# SCH_Broke-Knomi_2026-06-14.net
KiCad netlist of a schematic drawn in EasyEDA
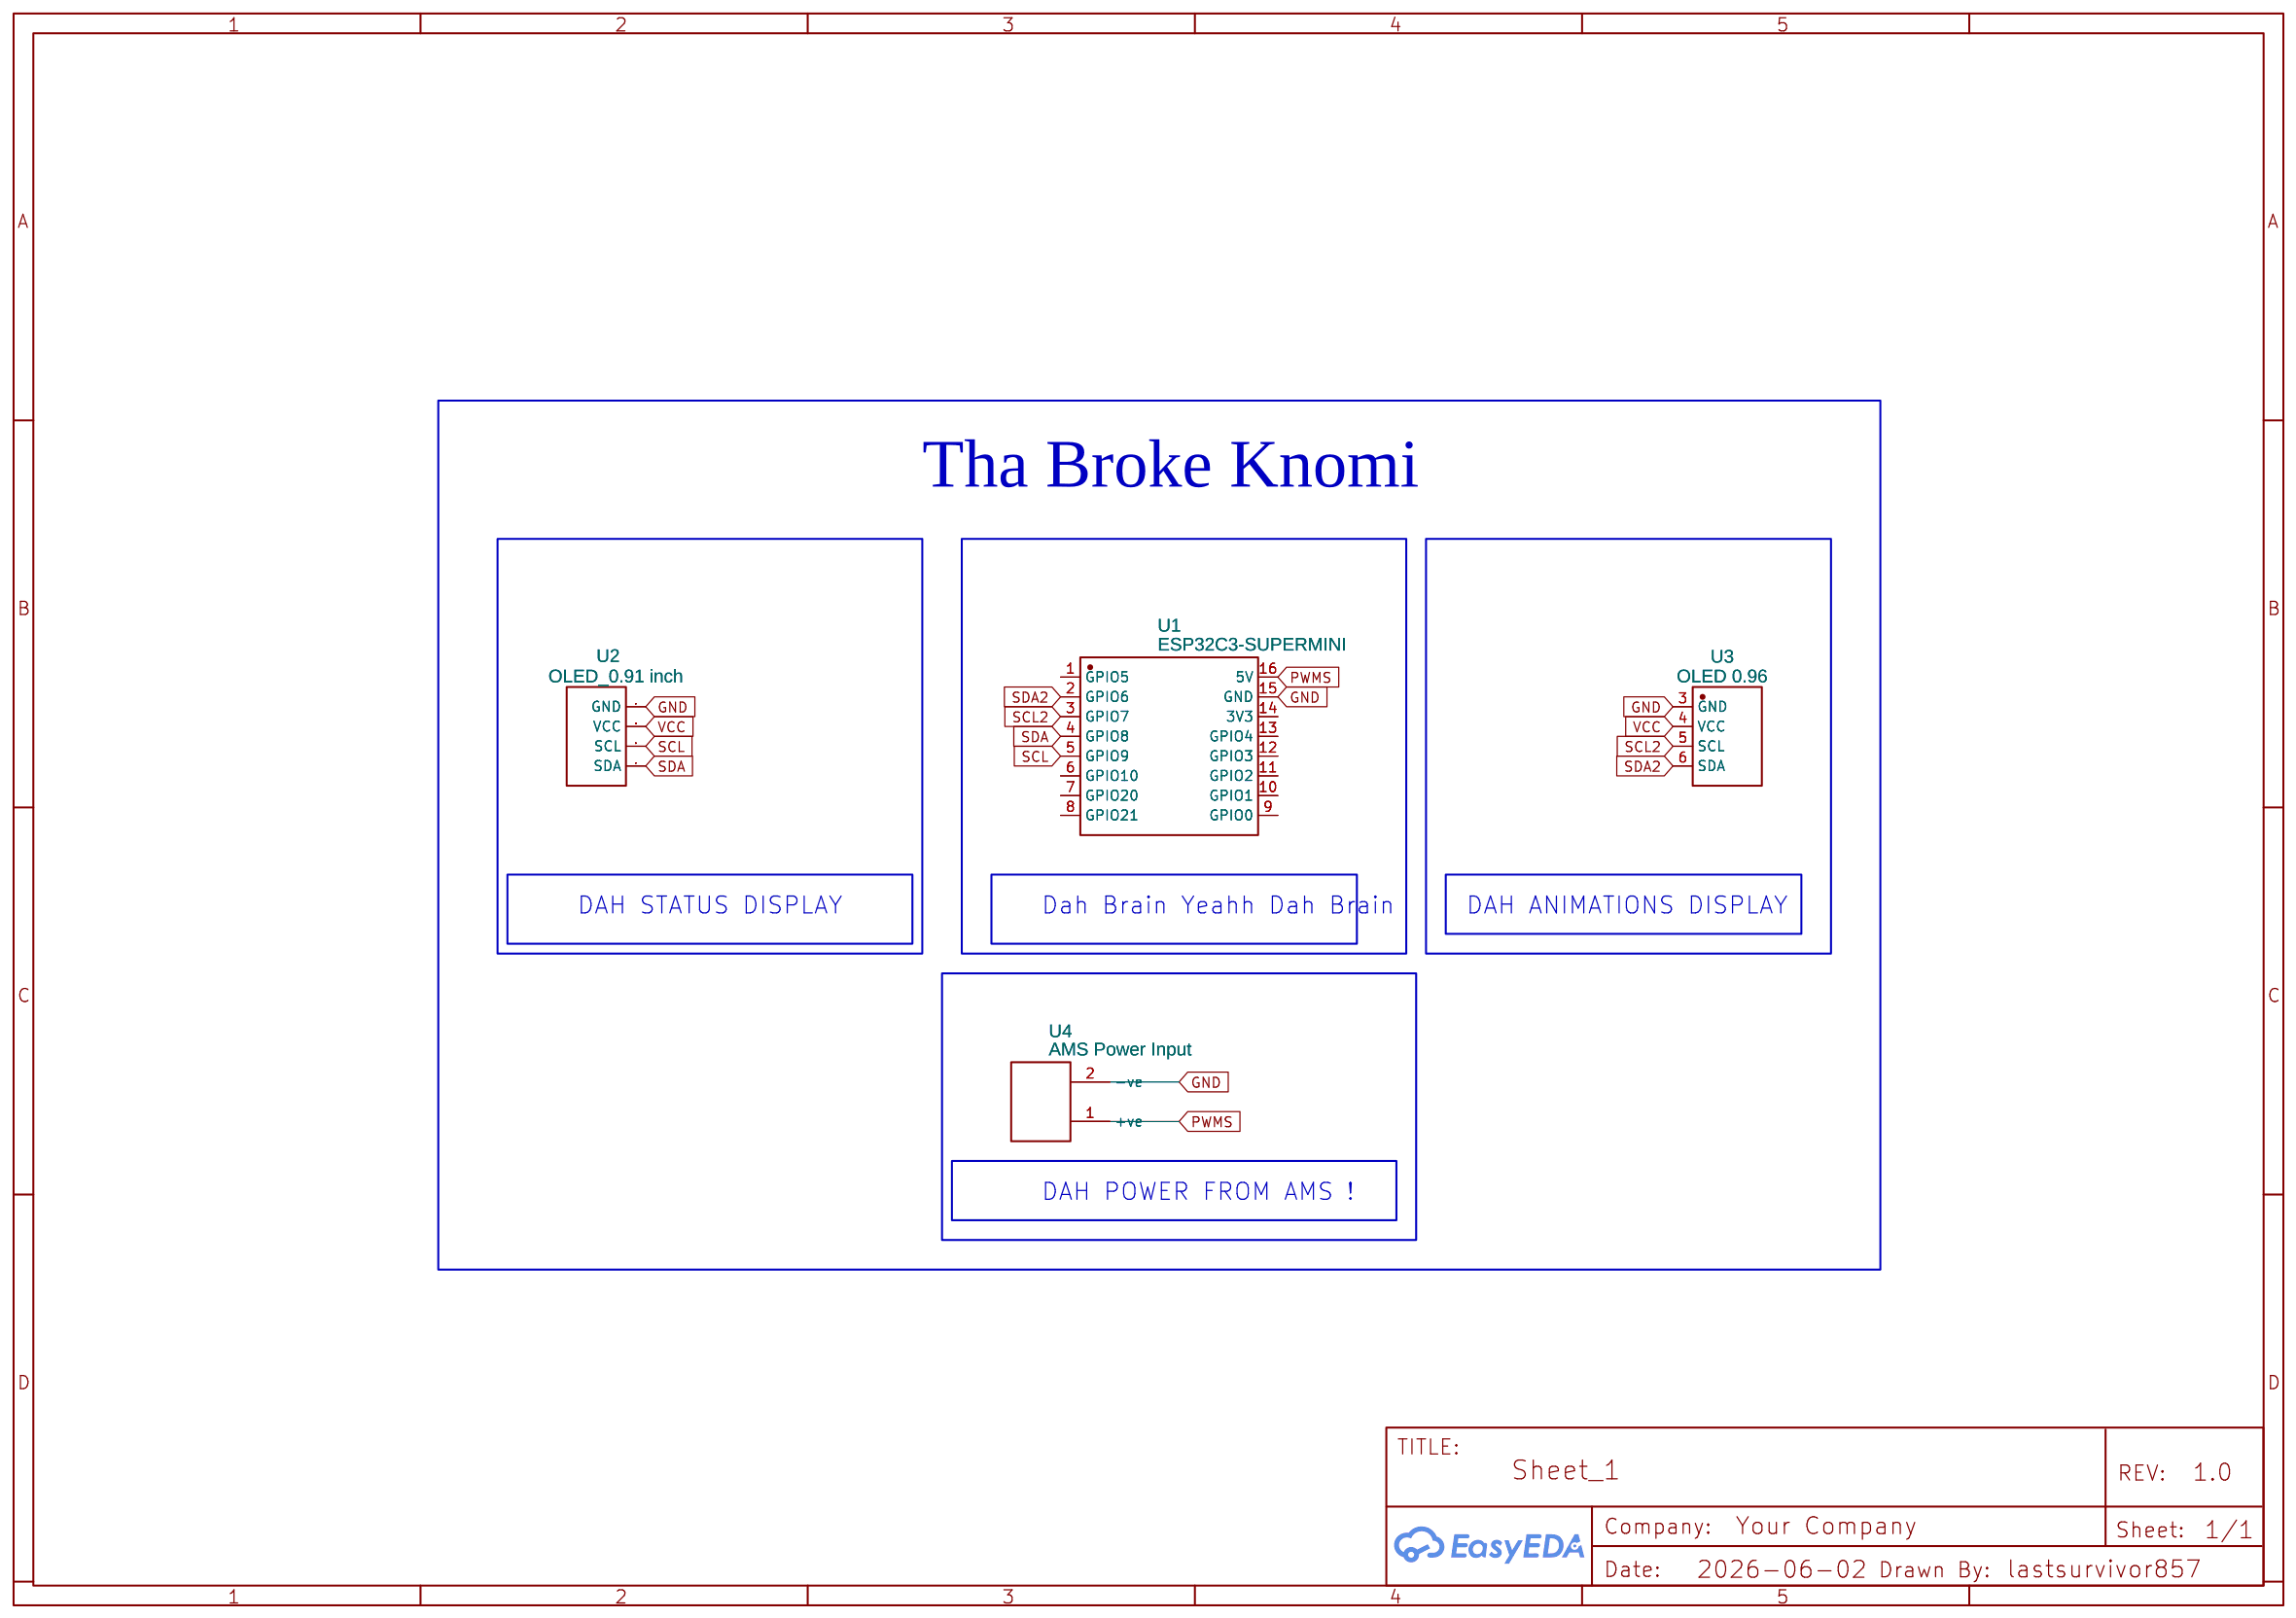
[diagram p0: schematic sheet]

(export (version "E")
  (design (tool "Eeschema 10.0.6"))
  (components
    (comp (ref "U1")
      (value "ESP32C3-SUPERMINI")
      (fields (field (name "Manufacturer Part") "ESP32C3-SuperMini"))
      (libsource (lib "") (part "ESP32C3-SUPERMINI"))
    )
    (comp (ref "U2") (value "OLED_0.91 inch") (libsource (lib "") (part "OLED_0.91 inch")))
    (comp (ref "U3")
      (value "OLED 0.96")
      (fields
        (field (name "Manufacturer Part") "ZJY096S0700BG01蓝色")
        (field (name "Manufacturer") "AZDelivery")
      )
      (libsource (lib "") (part "OLED 0.96 COPY"))
    )
    (comp (ref "U4") (value "AMS Power Input") (libsource (lib "") (part "Battery Terminal")))
  )
  (nets
    (net (code "1") (name "GND") (class "Default")
      (node (ref "U1") (pin "15") (pinfunction "GND_15") (pintype "unspecified"))
      (node (ref "U2") (pin "4") (pinfunction "GND_4") (pintype "unspecified"))
      (node (ref "U3") (pin "3") (pinfunction "GND_3") (pintype "unspecified"))
      (node (ref "U4") (pin "2") (pinfunction "-ve_2") (pintype "unspecified"))
    )
    (net (code "2") (name "PWMS") (class "Default")
      (node (ref "U1") (pin "16") (pinfunction "5V_16") (pintype "unspecified"))
      (node (ref "U4") (pin "1") (pinfunction "+ve_1") (pintype "unspecified"))
    )
    (net (code "3") (name "SCL") (class "Default")
      (node (ref "U1") (pin "5") (pinfunction "GPIO9_5") (pintype "unspecified"))
      (node (ref "U2") (pin "2") (pinfunction "SCL_2") (pintype "unspecified"))
    )
    (net (code "4") (name "SCL2") (class "Default")
      (node (ref "U1") (pin "3") (pinfunction "GPIO7_3") (pintype "unspecified"))
      (node (ref "U3") (pin "5") (pinfunction "SCL_5") (pintype "unspecified"))
    )
    (net (code "5") (name "SDA") (class "Default")
      (node (ref "U1") (pin "4") (pinfunction "GPIO8_4") (pintype "unspecified"))
      (node (ref "U2") (pin "1") (pinfunction "SDA_1") (pintype "unspecified"))
    )
    (net (code "6") (name "SDA2") (class "Default")
      (node (ref "U1") (pin "2") (pinfunction "GPIO6_2") (pintype "unspecified"))
      (node (ref "U3") (pin "6") (pinfunction "SDA_6") (pintype "unspecified"))
    )
    (net (code "7") (name "VCC") (class "Default")
      (node (ref "U2") (pin "3") (pinfunction "VCC_3") (pintype "unspecified"))
      (node (ref "U3") (pin "4") (pinfunction "VCC_4") (pintype "unspecified"))
    )
    (net (code "8") (name "unconnected-(U1-3V3-Pad14)") (class "Default")
      (node (ref "U1") (pin "14") (pinfunction "3V3_14") (pintype "unspecified"))
    )
    (net (code "9") (name "unconnected-(U1-GPIO0-Pad9)") (class "Default")
      (node (ref "U1") (pin "9") (pinfunction "GPIO0_9") (pintype "unspecified"))
    )
    (net (code "10") (name "unconnected-(U1-GPIO1-Pad10)") (class "Default")
      (node (ref "U1") (pin "10") (pinfunction "GPIO1_10") (pintype "unspecified"))
    )
    (net (code "11") (name "unconnected-(U1-GPIO2-Pad11)") (class "Default")
      (node (ref "U1") (pin "11") (pinfunction "GPIO2_11") (pintype "unspecified"))
    )
    (net (code "12") (name "unconnected-(U1-GPIO3-Pad12)") (class "Default")
      (node (ref "U1") (pin "12") (pinfunction "GPIO3_12") (pintype "unspecified"))
    )
    (net (code "13") (name "unconnected-(U1-GPIO4-Pad13)") (class "Default")
      (node (ref "U1") (pin "13") (pinfunction "GPIO4_13") (pintype "unspecified"))
    )
    (net (code "14") (name "unconnected-(U1-GPIO5-Pad1)") (class "Default")
      (node (ref "U1") (pin "1") (pinfunction "GPIO5_1") (pintype "unspecified"))
    )
    (net (code "15") (name "unconnected-(U1-GPIO10-Pad6)") (class "Default")
      (node (ref "U1") (pin "6") (pinfunction "GPIO10_6") (pintype "unspecified"))
    )
    (net (code "16") (name "unconnected-(U1-GPIO20-Pad7)") (class "Default")
      (node (ref "U1") (pin "7") (pinfunction "GPIO20_7") (pintype "unspecified"))
    )
    (net (code "17") (name "unconnected-(U1-GPIO21-Pad8)") (class "Default")
      (node (ref "U1") (pin "8") (pinfunction "GPIO21_8") (pintype "unspecified"))
    )
  )
)
